# untitled.net
KiCad netlist of a schematic drawn in EAGLE
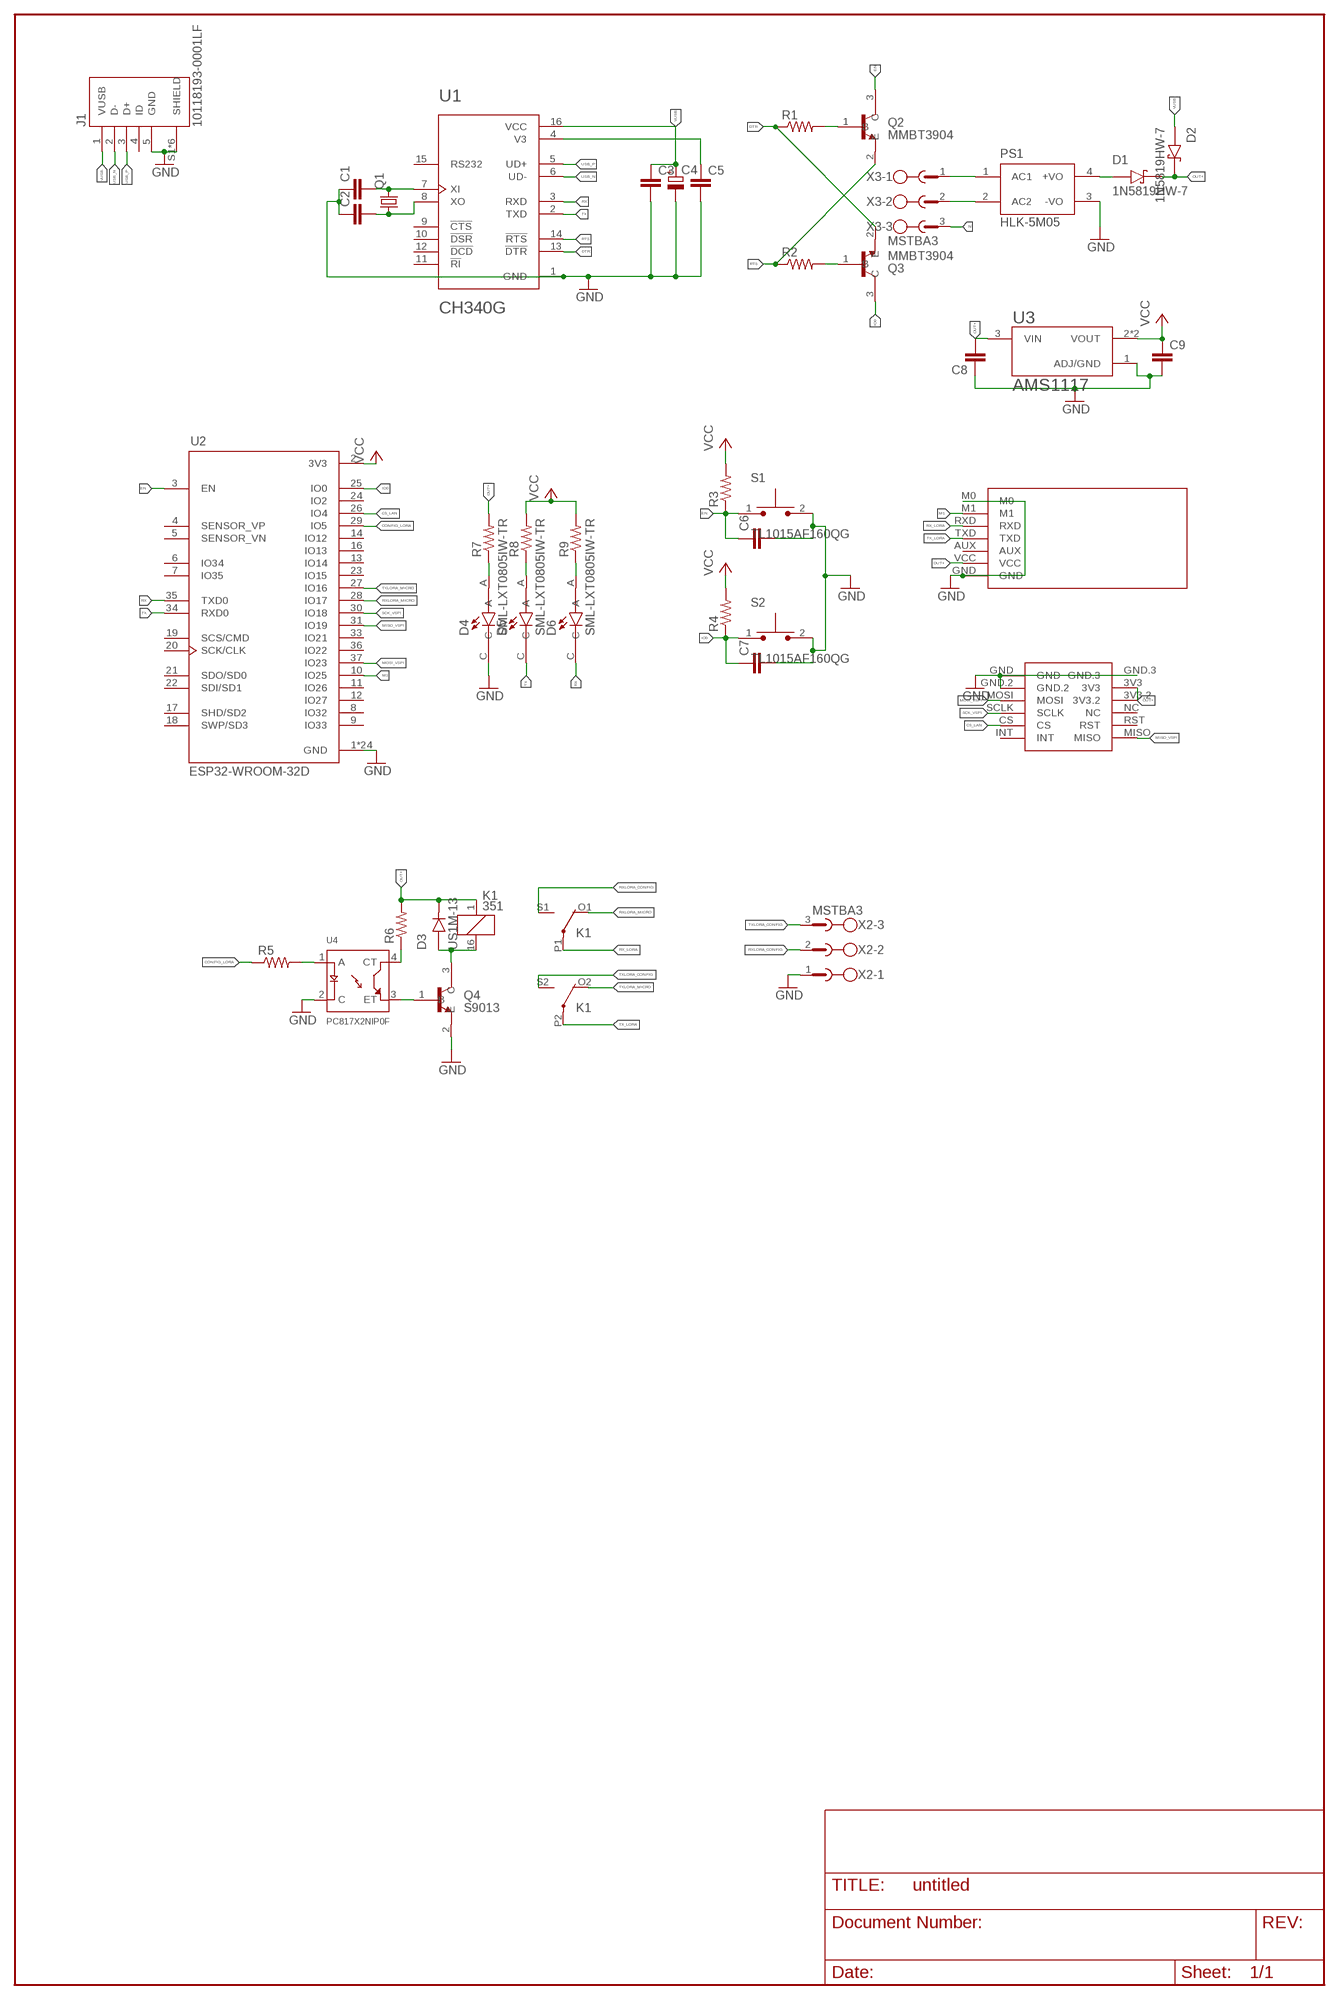
[diagram p0: schematic, sheet 1]

(export (version "E")
  (design (tool "Eeschema 10.0.6"))
  (components
    (comp (ref "C1")
      (value "C-EUC0805K")
      (footprint "eagle-import:C0805K")
      (libsource (lib "eagle-import") (part "C-EUC0805K"))
    )
    (comp (ref "C2")
      (value "C-EUC0805K")
      (footprint "eagle-import:C0805K")
      (libsource (lib "eagle-import") (part "C-EUC0805K"))
    )
    (comp (ref "C3")
      (value "C-EUC0805K")
      (footprint "eagle-import:C0805K")
      (libsource (lib "eagle-import") (part "C-EUC0805K"))
    )
    (comp (ref "C4")
      (value "CPOL-EU153CLV-0505")
      (footprint "eagle-import:153CLV-0505")
      (libsource (lib "eagle-import") (part "CPOL-EU153CLV-0505"))
    )
    (comp (ref "C5")
      (value "C-EUC0805K")
      (footprint "eagle-import:C0805K")
      (libsource (lib "eagle-import") (part "C-EUC0805K"))
    )
    (comp (ref "C6")
      (value "C-EUC0805K")
      (footprint "eagle-import:C0805K")
      (libsource (lib "eagle-import") (part "C-EUC0805K"))
    )
    (comp (ref "C7")
      (value "C-EUC0805K")
      (footprint "eagle-import:C0805K")
      (libsource (lib "eagle-import") (part "C-EUC0805K"))
    )
    (comp (ref "C8")
      (value "C-EUC0805K")
      (footprint "eagle-import:C0805K")
      (libsource (lib "eagle-import") (part "C-EUC0805K"))
    )
    (comp (ref "C9")
      (value "C-EUC0805K")
      (footprint "eagle-import:C0805K")
      (libsource (lib "eagle-import") (part "C-EUC0805K"))
    )
    (comp (ref "D1")
      (value "1N5819HW-7")
      (footprint "eagle-import:SOD3715X145N")
      (fields (field (name "MF") "Diodes Inc."))
      (libsource (lib "eagle-import") (part "1N5819HW-7"))
    )
    (comp (ref "D2")
      (value "1N5819HW-7")
      (footprint "eagle-import:SOD3715X145N")
      (fields (field (name "MF") "Diodes Inc."))
      (libsource (lib "eagle-import") (part "1N5819HW-7"))
    )
    (comp (ref "D3")
      (value "US1M-13")
      (footprint "eagle-import:DIOM5226X240N")
      (fields (field (name "MF") "Diodes Incorporated"))
      (libsource (lib "eagle-import") (part "US1M-13"))
    )
    (comp (ref "D4")
      (value "SML-LXT0805IW-TR")
      (footprint "eagle-import:LEDC2012X120N")
      (fields (field (name "MF") "Lumex Opto/Components"))
      (libsource (lib "eagle-import") (part "SML-LXT0805IW-TR"))
    )
    (comp (ref "D5")
      (value "SML-LXT0805IW-TR")
      (footprint "eagle-import:LEDC2012X120N")
      (fields (field (name "MF") "Lumex Opto/Components"))
      (libsource (lib "eagle-import") (part "SML-LXT0805IW-TR"))
    )
    (comp (ref "D6")
      (value "SML-LXT0805IW-TR")
      (footprint "eagle-import:LEDC2012X120N")
      (fields (field (name "MF") "Lumex Opto/Components"))
      (libsource (lib "eagle-import") (part "SML-LXT0805IW-TR"))
    )
    (comp (ref "EBYTEE220-900T22D1")
      (value "EBYTEE220-900T22D")
      (footprint "eagle-import:EBYTEE220-900T22D")
      (libsource (lib "eagle-import") (part "EBYTEE220-900T22D"))
    )
    (comp (ref "J1")
      (value "10118193-0001LF")
      (footprint "eagle-import:FCI_10118193-0001LF")
      (fields (field (name "MF") "FCI"))
      (libsource (lib "eagle-import") (part "10118193-0001LF"))
    )
    (comp (ref "K1")
      (value "351")
      (footprint "eagle-import:351")
      (libsource (lib "eagle-import") (part "351"))
    )
    (comp (ref "PS1")
      (value "HLK-5M05")
      (footprint "eagle-import:CONV_HLK-5M05")
      (fields (field (name "MF") "Hi-link"))
      (libsource (lib "eagle-import") (part "HLK-5M05"))
    )
    (comp (ref "Q1")
      (value "CRYSTALSM49")
      (footprint "eagle-import:SM49")
      (libsource (lib "eagle-import") (part "CRYSTALSM49"))
    )
    (comp (ref "Q2")
      (value "MMBT3904")
      (footprint "eagle-import:SOT95P240X120-3N")
      (fields (field (name "MF") "ON Semiconductor"))
      (libsource (lib "eagle-import") (part "MMBT3904"))
    )
    (comp (ref "Q3")
      (value "MMBT3904")
      (footprint "eagle-import:SOT95P240X120-3N")
      (fields (field (name "MF") "ON Semiconductor"))
      (libsource (lib "eagle-import") (part "MMBT3904"))
    )
    (comp (ref "Q4")
      (value "S9013")
      (footprint "eagle-import:SOT95P240X120-3N")
      (fields (field (name "MF") "JCET"))
      (libsource (lib "eagle-import") (part "S9013"))
    )
    (comp (ref "R1")
      (value "R-US_M0805")
      (footprint "eagle-import:M0805")
      (libsource (lib "eagle-import") (part "R-US_M0805"))
    )
    (comp (ref "R2")
      (value "R-US_M0805")
      (footprint "eagle-import:M0805")
      (libsource (lib "eagle-import") (part "R-US_M0805"))
    )
    (comp (ref "R3")
      (value "R-US_M0805")
      (footprint "eagle-import:M0805")
      (libsource (lib "eagle-import") (part "R-US_M0805"))
    )
    (comp (ref "R4")
      (value "R-US_M0805")
      (footprint "eagle-import:M0805")
      (libsource (lib "eagle-import") (part "R-US_M0805"))
    )
    (comp (ref "R5")
      (value "R-US_M0805")
      (footprint "eagle-import:M0805")
      (libsource (lib "eagle-import") (part "R-US_M0805"))
    )
    (comp (ref "R6")
      (value "R-US_M0805")
      (footprint "eagle-import:M0805")
      (libsource (lib "eagle-import") (part "R-US_M0805"))
    )
    (comp (ref "R7")
      (value "R-US_M0805")
      (footprint "eagle-import:M0805")
      (libsource (lib "eagle-import") (part "R-US_M0805"))
    )
    (comp (ref "R8")
      (value "R-US_M0805")
      (footprint "eagle-import:M0805")
      (libsource (lib "eagle-import") (part "R-US_M0805"))
    )
    (comp (ref "R9")
      (value "R-US_M0805")
      (footprint "eagle-import:M0805")
      (libsource (lib "eagle-import") (part "R-US_M0805"))
    )
    (comp (ref "S1")
      (value "TL1015AF160QG")
      (footprint "eagle-import:SW_TL1015AF160QG")
      (fields (field (name "MF") "E-Switch"))
      (libsource (lib "eagle-import") (part "TL1015AF160QG"))
    )
    (comp (ref "S2")
      (value "TL1015AF160QG")
      (footprint "eagle-import:SW_TL1015AF160QG")
      (fields (field (name "MF") "E-Switch"))
      (libsource (lib "eagle-import") (part "TL1015AF160QG"))
    )
    (comp (ref "U$1")
      (value "MINI_W5500")
      (footprint "eagle-import:MINI_W5500")
      (libsource (lib "eagle-import") (part "MINI_W5500"))
    )
    (comp (ref "U1")
      (value "CH340G")
      (footprint "eagle-import:SOIC127P600X180-16N")
      (fields (field (name "MF") "WCH") (field (name "MP") "Ch340G"))
      (libsource (lib "eagle-import") (part "CH340G"))
    )
    (comp (ref "U2")
      (value "ESP32-WROOM-32D")
      (footprint "eagle-import:MODULE_ESP32-WROOM-32D")
      (fields (field (name "MF") "Espressif Systems"))
      (libsource (lib "eagle-import") (part "ESP32-WROOM-32D"))
    )
    (comp (ref "U3")
      (value "AMS1117")
      (footprint "eagle-import:SOT229P700X180-4N")
      (fields (field (name "MF") "Advanced Monolithic Systems"))
      (libsource (lib "eagle-import") (part "AMS1117"))
    )
    (comp (ref "U4")
      (value "PC817X2NIP0F")
      (footprint "eagle-import:SOT254P975X400-4N")
      (fields (field (name "MF") "Sharp Microelectronics"))
      (libsource (lib "eagle-import") (part "PC817X2NIP0F"))
    )
    (comp (ref "X2")
      (value "MSTBA3")
      (footprint "eagle-import:MSTBA3")
      (fields (field (name "MF") "FARNELL") (field (name "MPN") "1757255"))
      (libsource (lib "eagle-import") (part "MSTBA3"))
    )
    (comp (ref "X3")
      (value "MSTBA3")
      (footprint "eagle-import:MSTBA3")
      (fields (field (name "MF") "FARNELL") (field (name "MPN") "1757255"))
      (libsource (lib "eagle-import") (part "MSTBA3"))
    )
  )
  (nets
    (net (code "1") (name "CONFIG_LORA") (class "Default")
      (node (ref "R5") (pin "1") (pinfunction "1_1") (pintype "passive"))
      (node (ref "U2") (pin "29") (pinfunction "IO5_29") (pintype "bidirectional"))
    )
    (net (code "2") (name "CS_LAN") (class "Default")
      (node (ref "U$1") (pin "CS") (pinfunction "CS_CS") (pintype "bidirectional"))
      (node (ref "U2") (pin "26") (pinfunction "IO4_26") (pintype "bidirectional"))
    )
    (net (code "3") (name "DTR") (class "Default")
      (node (ref "Q3") (pin "2") (pinfunction "E_2") (pintype "passive"))
      (node (ref "R1") (pin "1") (pinfunction "1_1") (pintype "passive"))
      (node (ref "U1") (pin "13") (pinfunction "~{DTR}_13") (pintype "output"))
    )
    (net (code "4") (name "EN") (class "Default")
      (node (ref "C6") (pin "1") (pinfunction "1_1") (pintype "passive"))
      (node (ref "Q2") (pin "3") (pinfunction "C_3") (pintype "passive"))
      (node (ref "R3") (pin "1") (pinfunction "1_1") (pintype "passive"))
      (node (ref "S1") (pin "1") (pinfunction "1_1") (pintype "passive"))
      (node (ref "U2") (pin "3") (pinfunction "EN_3") (pintype "input"))
    )
    (net (code "5") (name "GND") (class "Default")
      (node (ref "C1") (pin "1") (pinfunction "1_1") (pintype "passive"))
      (node (ref "C2") (pin "1") (pinfunction "1_1") (pintype "passive"))
      (node (ref "C3") (pin "2") (pinfunction "2_2") (pintype "passive"))
      (node (ref "C4") (pin "-") (pinfunction "-_-") (pintype "passive"))
      (node (ref "C5") (pin "2") (pinfunction "2_2") (pintype "passive"))
      (node (ref "C6") (pin "2") (pinfunction "2_2") (pintype "passive"))
      (node (ref "C7") (pin "2") (pinfunction "2_2") (pintype "passive"))
      (node (ref "C8") (pin "1") (pinfunction "1_1") (pintype "passive"))
      (node (ref "C9") (pin "2") (pinfunction "2_2") (pintype "passive"))
      (node (ref "D4") (pin "C") (pinfunction "C_C") (pintype "passive"))
      (node (ref "EBYTEE220-900T22D1") (pin "GND") (pinfunction "GND_GND") (pintype "bidirectional"))
      (node (ref "EBYTEE220-900T22D1") (pin "M0") (pinfunction "M0_M0") (pintype "bidirectional"))
      (node (ref "J1") (pin "5") (pinfunction "GND_5") (pintype "passive"))
      (node (ref "J1") (pin "S1") (pinfunction "SHIELD_S1") (pintype "passive"))
      (node (ref "J1") (pin "S2") (pinfunction "SHIELD_S2") (pintype "passive"))
      (node (ref "J1") (pin "S3") (pinfunction "SHIELD_S3") (pintype "passive"))
      (node (ref "J1") (pin "S4") (pinfunction "SHIELD_S4") (pintype "passive"))
      (node (ref "J1") (pin "S5") (pinfunction "SHIELD_S5") (pintype "passive"))
      (node (ref "J1") (pin "S6") (pinfunction "SHIELD_S6") (pintype "passive"))
      (node (ref "PS1") (pin "3") (pinfunction "-VO_3") (pintype "output"))
      (node (ref "Q4") (pin "2") (pinfunction "E_2") (pintype "passive"))
      (node (ref "S1") (pin "2") (pinfunction "2_2") (pintype "passive"))
      (node (ref "S2") (pin "2") (pinfunction "2_2") (pintype "passive"))
      (node (ref "U$1") (pin "GND") (pinfunction "GND_GND") (pintype "bidirectional"))
      (node (ref "U$1") (pin "GND.2") (pinfunction "GND.2_GND.2") (pintype "bidirectional"))
      (node (ref "U$1") (pin "GND.3") (pinfunction "GND.3_GND.3") (pintype "bidirectional"))
      (node (ref "U1") (pin "1") (pinfunction "GND_1") (pintype "power_in"))
      (node (ref "U2") (pin "1") (pinfunction "GND_1") (pintype "power_in"))
      (node (ref "U2") (pin "15") (pinfunction "GND_15") (pintype "power_in"))
      (node (ref "U2") (pin "38") (pinfunction "GND_38") (pintype "power_in"))
      (node (ref "U2") (pin "39_1") (pinfunction "GND_39_1") (pintype "power_in"))
      (node (ref "U2") (pin "39_10") (pinfunction "GND_39_10") (pintype "power_in"))
      (node (ref "U2") (pin "39_11") (pinfunction "GND_39_11") (pintype "power_in"))
      (node (ref "U2") (pin "39_12") (pinfunction "GND_39_12") (pintype "power_in"))
      (node (ref "U2") (pin "39_13") (pinfunction "GND_39_13") (pintype "power_in"))
      (node (ref "U2") (pin "39_14") (pinfunction "GND_39_14") (pintype "power_in"))
      (node (ref "U2") (pin "39_15") (pinfunction "GND_39_15") (pintype "power_in"))
      (node (ref "U2") (pin "39_16") (pinfunction "GND_39_16") (pintype "power_in"))
      (node (ref "U2") (pin "39_17") (pinfunction "GND_39_17") (pintype "power_in"))
      (node (ref "U2") (pin "39_18") (pinfunction "GND_39_18") (pintype "power_in"))
      (node (ref "U2") (pin "39_19") (pinfunction "GND_39_19") (pintype "power_in"))
      (node (ref "U2") (pin "39_2") (pinfunction "GND_39_2") (pintype "power_in"))
      (node (ref "U2") (pin "39_20") (pinfunction "GND_39_20") (pintype "power_in"))
      (node (ref "U2") (pin "39_21") (pinfunction "GND_39_21") (pintype "power_in"))
      (node (ref "U2") (pin "39_3") (pinfunction "GND_39_3") (pintype "power_in"))
      (node (ref "U2") (pin "39_4") (pinfunction "GND_39_4") (pintype "power_in"))
      (node (ref "U2") (pin "39_5") (pinfunction "GND_39_5") (pintype "power_in"))
      (node (ref "U2") (pin "39_6") (pinfunction "GND_39_6") (pintype "power_in"))
      (node (ref "U2") (pin "39_7") (pinfunction "GND_39_7") (pintype "power_in"))
      (node (ref "U2") (pin "39_8") (pinfunction "GND_39_8") (pintype "power_in"))
      (node (ref "U2") (pin "39_9") (pinfunction "GND_39_9") (pintype "power_in"))
      (node (ref "U3") (pin "1") (pinfunction "ADJ/GND_1") (pintype "power_in"))
      (node (ref "U4") (pin "2") (pinfunction "C_2") (pintype "passive"))
      (node (ref "X2") (pin "1") (pinfunction "1_1") (pintype "passive"))
    )
    (net (code "6") (name "IO0") (class "Default")
      (node (ref "C7") (pin "1") (pinfunction "1_1") (pintype "passive"))
      (node (ref "Q3") (pin "3") (pinfunction "C_3") (pintype "passive"))
      (node (ref "R4") (pin "1") (pinfunction "1_1") (pintype "passive"))
      (node (ref "S2") (pin "1") (pinfunction "1_1") (pintype "passive"))
      (node (ref "U2") (pin "25") (pinfunction "IO0_25") (pintype "bidirectional"))
    )
    (net (code "7") (name "M1") (class "Default")
      (node (ref "EBYTEE220-900T22D1") (pin "M1") (pinfunction "M1_M1") (pintype "bidirectional"))
      (node (ref "U2") (pin "10") (pinfunction "IO25_10") (pintype "bidirectional"))
    )
    (net (code "8") (name "MISO_VSPI") (class "Default")
      (node (ref "U$1") (pin "MISO") (pinfunction "MISO_MISO") (pintype "bidirectional"))
      (node (ref "U2") (pin "31") (pinfunction "IO19_31") (pintype "bidirectional"))
    )
    (net (code "9") (name "MOSI_VSPI") (class "Default")
      (node (ref "U$1") (pin "MOSI") (pinfunction "MOSI_MOSI") (pintype "bidirectional"))
      (node (ref "U2") (pin "37") (pinfunction "IO23_37") (pintype "bidirectional"))
    )
    (net (code "10") (name "N") (class "Default")
      (node (ref "X3") (pin "3") (pinfunction "1_3") (pintype "passive"))
    )
    (net (code "11") (name "Net-(D4-PadA)") (class "Default")
      (node (ref "D4") (pin "A") (pinfunction "A_A") (pintype "passive"))
      (node (ref "R7") (pin "1") (pinfunction "1_1") (pintype "passive"))
    )
    (net (code "12") (name "Net-(D5-PadA)") (class "Default")
      (node (ref "D5") (pin "A") (pinfunction "A_A") (pintype "passive"))
      (node (ref "R8") (pin "1") (pinfunction "1_1") (pintype "passive"))
    )
    (net (code "13") (name "Net-(D6-PadA)") (class "Default")
      (node (ref "D6") (pin "A") (pinfunction "A_A") (pintype "passive"))
      (node (ref "R9") (pin "1") (pinfunction "1_1") (pintype "passive"))
    )
    (net (code "14") (name "Net-(K1A-2)") (class "Default")
      (node (ref "D3") (pin "A") (pinfunction "A_A") (pintype "passive"))
      (node (ref "K1") (pin "16") (pinfunction "2_16") (pintype "passive"))
      (node (ref "Q4") (pin "3") (pinfunction "C_3") (pintype "passive"))
    )
    (net (code "15") (name "Net-(PS1-+VO)") (class "Default")
      (node (ref "D1") (pin "A") (pinfunction "A_A") (pintype "passive"))
      (node (ref "PS1") (pin "4") (pinfunction "+VO_4") (pintype "output"))
    )
    (net (code "16") (name "Net-(PS1-AC1)") (class "Default")
      (node (ref "PS1") (pin "1") (pinfunction "AC1_1") (pintype "input"))
      (node (ref "X3") (pin "1") (pinfunction "1_1") (pintype "passive"))
    )
    (net (code "17") (name "Net-(PS1-AC2)") (class "Default")
      (node (ref "PS1") (pin "2") (pinfunction "AC2_2") (pintype "input"))
      (node (ref "X3") (pin "2") (pinfunction "1_2") (pintype "passive"))
    )
    (net (code "18") (name "Net-(Q2-B)") (class "Default")
      (node (ref "Q2") (pin "1") (pinfunction "B_1") (pintype "passive"))
      (node (ref "R1") (pin "2") (pinfunction "2_2") (pintype "passive"))
    )
    (net (code "19") (name "Net-(Q3-B)") (class "Default")
      (node (ref "Q3") (pin "1") (pinfunction "B_1") (pintype "passive"))
      (node (ref "R2") (pin "2") (pinfunction "2_2") (pintype "passive"))
    )
    (net (code "20") (name "Net-(Q4-B)") (class "Default")
      (node (ref "Q4") (pin "1") (pinfunction "B_1") (pintype "passive"))
      (node (ref "U4") (pin "3") (pinfunction "ET_3") (pintype "passive"))
    )
    (net (code "21") (name "Net-(U1-V3)") (class "Default")
      (node (ref "C5") (pin "1") (pinfunction "1_1") (pintype "passive"))
      (node (ref "U1") (pin "4") (pinfunction "V3_4") (pintype "power_in"))
    )
    (net (code "22") (name "Net-(U1-XI)") (class "Default")
      (node (ref "C1") (pin "2") (pinfunction "2_2") (pintype "passive"))
      (node (ref "Q1") (pin "2") (pinfunction "2_2") (pintype "passive"))
      (node (ref "U1") (pin "7") (pinfunction "XI_7") (pintype "input"))
    )
    (net (code "23") (name "Net-(U1-XO)") (class "Default")
      (node (ref "C2") (pin "2") (pinfunction "2_2") (pintype "passive"))
      (node (ref "Q1") (pin "1") (pinfunction "1_1") (pintype "passive"))
      (node (ref "U1") (pin "8") (pinfunction "XO_8") (pintype "output"))
    )
    (net (code "24") (name "Net-(U4-A)") (class "Default")
      (node (ref "R5") (pin "2") (pinfunction "2_2") (pintype "passive"))
      (node (ref "U4") (pin "1") (pinfunction "A_1") (pintype "passive"))
    )
    (net (code "25") (name "Net-(U4-CT)") (class "Default")
      (node (ref "R6") (pin "1") (pinfunction "1_1") (pintype "passive"))
      (node (ref "U4") (pin "4") (pinfunction "CT_4") (pintype "passive"))
    )
    (net (code "26") (name "OUT+") (class "Default")
      (node (ref "C8") (pin "2") (pinfunction "2_2") (pintype "passive"))
      (node (ref "D1") (pin "C") (pinfunction "K_C") (pintype "passive"))
      (node (ref "D2") (pin "C") (pinfunction "K_C") (pintype "passive"))
      (node (ref "D3") (pin "C") (pinfunction "K_C") (pintype "passive"))
      (node (ref "EBYTEE220-900T22D1") (pin "VCC") (pinfunction "VCC_VCC") (pintype "bidirectional"))
      (node (ref "K1") (pin "1") (pinfunction "1_1") (pintype "passive"))
      (node (ref "R6") (pin "2") (pinfunction "2_2") (pintype "passive"))
      (node (ref "R7") (pin "2") (pinfunction "2_2") (pintype "passive"))
      (node (ref "U$1") (pin "3V3") (pinfunction "3V3_3V3") (pintype "bidirectional"))
      (node (ref "U$1") (pin "3V3.2") (pinfunction "3V3.2_3V3.2") (pintype "bidirectional"))
      (node (ref "U3") (pin "3") (pinfunction "VIN_3") (pintype "input"))
    )
    (net (code "27") (name "RTS") (class "Default")
      (node (ref "Q2") (pin "2") (pinfunction "E_2") (pintype "passive"))
      (node (ref "R2") (pin "1") (pinfunction "1_1") (pintype "passive"))
      (node (ref "U1") (pin "14") (pinfunction "~{RTS}_14") (pintype "output"))
    )
    (net (code "28") (name "RX") (class "Default")
      (node (ref "D6") (pin "C") (pinfunction "C_C") (pintype "passive"))
      (node (ref "U1") (pin "3") (pinfunction "RXD_3") (pintype "input"))
      (node (ref "U2") (pin "35") (pinfunction "TXD0_35") (pintype "bidirectional"))
    )
    (net (code "29") (name "RXLORA_CONFIG") (class "Default")
      (node (ref "K1") (pin "S1") (pinfunction "S_S1") (pintype "passive"))
      (node (ref "X2") (pin "2") (pinfunction "1_2") (pintype "passive"))
    )
    (net (code "30") (name "RXLORA_MICRO") (class "Default")
      (node (ref "K1") (pin "O1") (pinfunction "O_O1") (pintype "passive"))
      (node (ref "U2") (pin "28") (pinfunction "IO17_28") (pintype "bidirectional"))
    )
    (net (code "31") (name "RX_LORA") (class "Default")
      (node (ref "EBYTEE220-900T22D1") (pin "RXD") (pinfunction "RXD_RXD") (pintype "bidirectional"))
      (node (ref "K1") (pin "P1") (pinfunction "P_P1") (pintype "passive"))
    )
    (net (code "32") (name "SCK_VSPI") (class "Default")
      (node (ref "U$1") (pin "SCLK") (pinfunction "SCLK_SCLK") (pintype "bidirectional"))
      (node (ref "U2") (pin "30") (pinfunction "IO18_30") (pintype "bidirectional"))
    )
    (net (code "33") (name "TX") (class "Default")
      (node (ref "D5") (pin "C") (pinfunction "C_C") (pintype "passive"))
      (node (ref "U1") (pin "2") (pinfunction "TXD_2") (pintype "output"))
      (node (ref "U2") (pin "34") (pinfunction "RXD0_34") (pintype "bidirectional"))
    )
    (net (code "34") (name "TXLORA_CONFIG") (class "Default")
      (node (ref "K1") (pin "S2") (pinfunction "S_S2") (pintype "passive"))
      (node (ref "X2") (pin "3") (pinfunction "1_3") (pintype "passive"))
    )
    (net (code "35") (name "TXLORA_MICRO") (class "Default")
      (node (ref "K1") (pin "O2") (pinfunction "O_O2") (pintype "passive"))
      (node (ref "U2") (pin "27") (pinfunction "IO16_27") (pintype "bidirectional"))
    )
    (net (code "36") (name "TX_LORA") (class "Default")
      (node (ref "EBYTEE220-900T22D1") (pin "TXD") (pinfunction "TXD_TXD") (pintype "bidirectional"))
      (node (ref "K1") (pin "P2") (pinfunction "P_P2") (pintype "passive"))
    )
    (net (code "37") (name "USB_N") (class "Default")
      (node (ref "J1") (pin "2") (pinfunction "D-_2") (pintype "passive"))
      (node (ref "U1") (pin "6") (pinfunction "UD-_6") (pintype "bidirectional"))
    )
    (net (code "38") (name "USB_P") (class "Default")
      (node (ref "J1") (pin "3") (pinfunction "D+_3") (pintype "passive"))
      (node (ref "U1") (pin "5") (pinfunction "UD+_5") (pintype "bidirectional"))
    )
    (net (code "39") (name "VCC") (class "Default")
      (node (ref "C9") (pin "1") (pinfunction "1_1") (pintype "passive"))
      (node (ref "R3") (pin "2") (pinfunction "2_2") (pintype "passive"))
      (node (ref "R4") (pin "2") (pinfunction "2_2") (pintype "passive"))
      (node (ref "R8") (pin "2") (pinfunction "2_2") (pintype "passive"))
      (node (ref "R9") (pin "2") (pinfunction "2_2") (pintype "passive"))
      (node (ref "U2") (pin "2") (pinfunction "3V3_2") (pintype "power_in"))
      (node (ref "U3") (pin "2") (pinfunction "VOUT_2") (pintype "output"))
      (node (ref "U3") (pin "4") (pinfunction "VOUT_4") (pintype "output"))
    )
    (net (code "40") (name "VUSB") (class "Default")
      (node (ref "C3") (pin "1") (pinfunction "1_1") (pintype "passive"))
      (node (ref "C4") (pin "+") (pinfunction "+_+") (pintype "passive"))
      (node (ref "D2") (pin "A") (pinfunction "A_A") (pintype "passive"))
      (node (ref "J1") (pin "1") (pinfunction "VUSB_1") (pintype "passive"))
      (node (ref "U1") (pin "16") (pinfunction "VCC_16") (pintype "power_in"))
    )
    (net (code "41") (name "unconnected-(EBYTEE220-900T22D1-PadAUX)") (class "Default")
      (node (ref "EBYTEE220-900T22D1") (pin "AUX") (pinfunction "AUX_AUX") (pintype "bidirectional"))
    )
    (net (code "42") (name "unconnected-(J1-ID-Pad4)") (class "Default")
      (node (ref "J1") (pin "4") (pinfunction "ID_4") (pintype "passive"))
    )
    (net (code "43") (name "unconnected-(U$1-PadINT)") (class "Default")
      (node (ref "U$1") (pin "INT") (pinfunction "INT_INT") (pintype "bidirectional"))
    )
    (net (code "44") (name "unconnected-(U$1-PadNC)") (class "Default")
      (node (ref "U$1") (pin "NC") (pinfunction "NC_NC") (pintype "bidirectional"))
    )
    (net (code "45") (name "unconnected-(U$1-PadRST)") (class "Default")
      (node (ref "U$1") (pin "RST") (pinfunction "RST_RST") (pintype "bidirectional"))
    )
    (net (code "46") (name "unconnected-(U1-RS232-Pad15)") (class "Default")
      (node (ref "U1") (pin "15") (pinfunction "RS232_15") (pintype "input"))
    )
    (net (code "47") (name "unconnected-(U1-~{CTS}-Pad9)") (class "Default")
      (node (ref "U1") (pin "9") (pinfunction "~{CTS}_9") (pintype "input"))
    )
    (net (code "48") (name "unconnected-(U1-~{DCD}-Pad12)") (class "Default")
      (node (ref "U1") (pin "12") (pinfunction "~{DCD}_12") (pintype "input"))
    )
    (net (code "49") (name "unconnected-(U1-~{DSR}-Pad10)") (class "Default")
      (node (ref "U1") (pin "10") (pinfunction "~{DSR}_10") (pintype "input"))
    )
    (net (code "50") (name "unconnected-(U1-~{RI}-Pad11)") (class "Default")
      (node (ref "U1") (pin "11") (pinfunction "~{RI}_11") (pintype "input"))
    )
    (net (code "51") (name "unconnected-(U2-IO2-Pad24)") (class "Default")
      (node (ref "U2") (pin "24") (pinfunction "IO2_24") (pintype "bidirectional"))
    )
    (net (code "52") (name "unconnected-(U2-IO12-Pad14)") (class "Default")
      (node (ref "U2") (pin "14") (pinfunction "IO12_14") (pintype "bidirectional"))
    )
    (net (code "53") (name "unconnected-(U2-IO13-Pad16)") (class "Default")
      (node (ref "U2") (pin "16") (pinfunction "IO13_16") (pintype "bidirectional"))
    )
    (net (code "54") (name "unconnected-(U2-IO14-Pad13)") (class "Default")
      (node (ref "U2") (pin "13") (pinfunction "IO14_13") (pintype "bidirectional"))
    )
    (net (code "55") (name "unconnected-(U2-IO15-Pad23)") (class "Default")
      (node (ref "U2") (pin "23") (pinfunction "IO15_23") (pintype "bidirectional"))
    )
    (net (code "56") (name "unconnected-(U2-IO21-Pad33)") (class "Default")
      (node (ref "U2") (pin "33") (pinfunction "IO21_33") (pintype "bidirectional"))
    )
    (net (code "57") (name "unconnected-(U2-IO22-Pad36)") (class "Default")
      (node (ref "U2") (pin "36") (pinfunction "IO22_36") (pintype "bidirectional"))
    )
    (net (code "58") (name "unconnected-(U2-IO26-Pad11)") (class "Default")
      (node (ref "U2") (pin "11") (pinfunction "IO26_11") (pintype "bidirectional"))
    )
    (net (code "59") (name "unconnected-(U2-IO27-Pad12)") (class "Default")
      (node (ref "U2") (pin "12") (pinfunction "IO27_12") (pintype "bidirectional"))
    )
    (net (code "60") (name "unconnected-(U2-IO32-Pad8)") (class "Default")
      (node (ref "U2") (pin "8") (pinfunction "IO32_8") (pintype "bidirectional"))
    )
    (net (code "61") (name "unconnected-(U2-IO33-Pad9)") (class "Default")
      (node (ref "U2") (pin "9") (pinfunction "IO33_9") (pintype "bidirectional"))
    )
    (net (code "62") (name "unconnected-(U2-IO34-Pad6)") (class "Default")
      (node (ref "U2") (pin "6") (pinfunction "IO34_6") (pintype "input"))
    )
    (net (code "63") (name "unconnected-(U2-IO35-Pad7)") (class "Default")
      (node (ref "U2") (pin "7") (pinfunction "IO35_7") (pintype "input"))
    )
    (net (code "64") (name "unconnected-(U2-SCK{slash}CLK-Pad20)") (class "Default")
      (node (ref "U2") (pin "20") (pinfunction "SCK/CLK_20") (pintype "bidirectional"))
    )
    (net (code "65") (name "unconnected-(U2-SCS{slash}CMD-Pad19)") (class "Default")
      (node (ref "U2") (pin "19") (pinfunction "SCS/CMD_19") (pintype "bidirectional"))
    )
    (net (code "66") (name "unconnected-(U2-SDI{slash}SD1-Pad22)") (class "Default")
      (node (ref "U2") (pin "22") (pinfunction "SDI/SD1_22") (pintype "bidirectional"))
    )
    (net (code "67") (name "unconnected-(U2-SDO{slash}SD0-Pad21)") (class "Default")
      (node (ref "U2") (pin "21") (pinfunction "SDO/SD0_21") (pintype "bidirectional"))
    )
    (net (code "68") (name "unconnected-(U2-SENSOR_VN-Pad5)") (class "Default")
      (node (ref "U2") (pin "5") (pinfunction "SENSOR_VN_5") (pintype "input"))
    )
    (net (code "69") (name "unconnected-(U2-SENSOR_VP-Pad4)") (class "Default")
      (node (ref "U2") (pin "4") (pinfunction "SENSOR_VP_4") (pintype "input"))
    )
    (net (code "70") (name "unconnected-(U2-SHD{slash}SD2-Pad17)") (class "Default")
      (node (ref "U2") (pin "17") (pinfunction "SHD/SD2_17") (pintype "bidirectional"))
    )
    (net (code "71") (name "unconnected-(U2-SWP{slash}SD3-Pad18)") (class "Default")
      (node (ref "U2") (pin "18") (pinfunction "SWP/SD3_18") (pintype "bidirectional"))
    )
  )
)
